# GND_STN.net
KiCad netlist of a schematic drawn in EAGLE
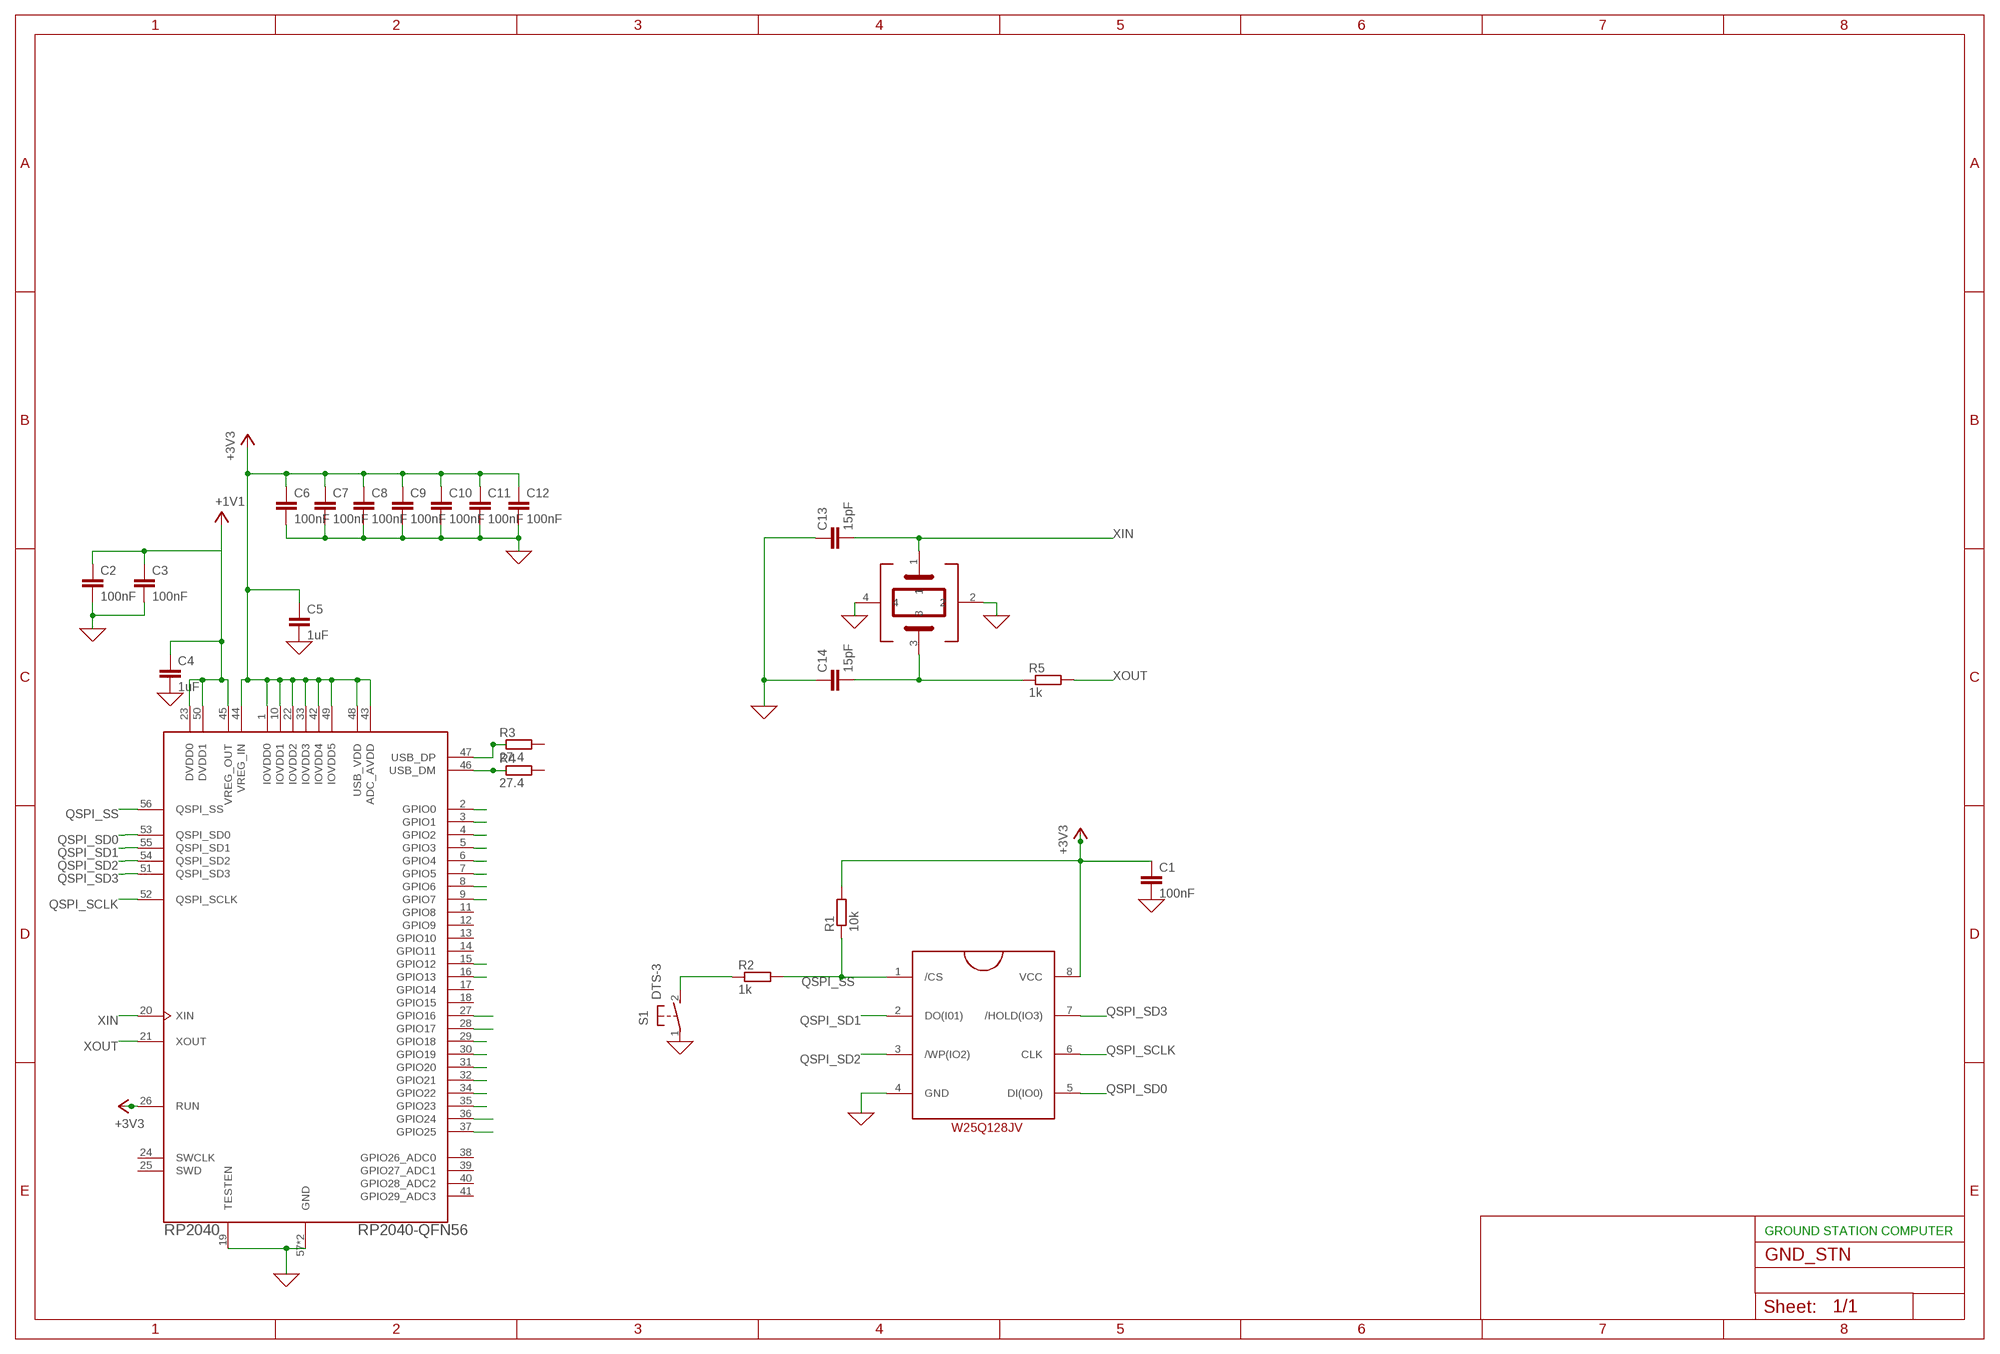
[diagram p0: schematic, sheet 1]

(export (version "E")
  (design (tool "Eeschema 10.0.6"))
  (components
    (comp (ref "C1")
      (value "100nF")
      (footprint "eagle-import:C0603")
      (libsource (lib "eagle-import") (part "C-EUC0603"))
    )
    (comp (ref "C2")
      (value "100nF")
      (footprint "eagle-import:C0603")
      (libsource (lib "eagle-import") (part "C-EUC0603"))
    )
    (comp (ref "C3")
      (value "100nF")
      (footprint "eagle-import:C0603")
      (libsource (lib "eagle-import") (part "C-EUC0603"))
    )
    (comp (ref "C4")
      (value "1uF")
      (footprint "eagle-import:C0603")
      (libsource (lib "eagle-import") (part "C-EUC0603"))
    )
    (comp (ref "C5")
      (value "1uF")
      (footprint "eagle-import:C0603")
      (libsource (lib "eagle-import") (part "C-EUC0603"))
    )
    (comp (ref "C6")
      (value "100nF")
      (footprint "eagle-import:C0603")
      (libsource (lib "eagle-import") (part "C-EUC0603"))
    )
    (comp (ref "C7")
      (value "100nF")
      (footprint "eagle-import:C0603")
      (libsource (lib "eagle-import") (part "C-EUC0603"))
    )
    (comp (ref "C8")
      (value "100nF")
      (footprint "eagle-import:C0603")
      (libsource (lib "eagle-import") (part "C-EUC0603"))
    )
    (comp (ref "C9")
      (value "100nF")
      (footprint "eagle-import:C0603")
      (libsource (lib "eagle-import") (part "C-EUC0603"))
    )
    (comp (ref "C10")
      (value "100nF")
      (footprint "eagle-import:C0603")
      (libsource (lib "eagle-import") (part "C-EUC0603"))
    )
    (comp (ref "C11")
      (value "100nF")
      (footprint "eagle-import:C0603")
      (libsource (lib "eagle-import") (part "C-EUC0603"))
    )
    (comp (ref "C12")
      (value "100nF")
      (footprint "eagle-import:C0603")
      (libsource (lib "eagle-import") (part "C-EUC0603"))
    )
    (comp (ref "C13")
      (value "15pF")
      (footprint "eagle-import:C0603")
      (libsource (lib "eagle-import") (part "C-EUC0603"))
    )
    (comp (ref "C14")
      (value "15pF")
      (footprint "eagle-import:C0603")
      (libsource (lib "eagle-import") (part "C-EUC0603"))
    )
    (comp (ref "R1")
      (value "10k")
      (footprint "eagle-import:R0603")
      (libsource (lib "eagle-import") (part "R-EU_R0603"))
    )
    (comp (ref "R2")
      (value "1k")
      (footprint "eagle-import:R0603")
      (libsource (lib "eagle-import") (part "R-EU_R0603"))
    )
    (comp (ref "R3")
      (value "27.4")
      (footprint "eagle-import:R0603")
      (libsource (lib "eagle-import") (part "R-EU_R0603"))
    )
    (comp (ref "R4")
      (value "27.4")
      (footprint "eagle-import:R0603")
      (libsource (lib "eagle-import") (part "R-EU_R0603"))
    )
    (comp (ref "R5")
      (value "1k")
      (footprint "eagle-import:R0603")
      (libsource (lib "eagle-import") (part "R-EU_R0603"))
    )
    (comp (ref "RP2040")
      (value "RP2040-QFN56")
      (footprint "eagle-import:RP2040-QFN-56")
      (libsource (lib "eagle-import") (part "RP2040-QFN56"))
    )
    (comp (ref "S1")
      (value "DTS-3")
      (footprint "eagle-import:DTS-3")
      (fields (field (name "MF") "APEM Inc."))
      (libsource (lib "eagle-import") (part "DTS-3"))
    )
    (comp (ref "U$1")
      (value "ABM8-272-T3")
      (footprint "eagle-import:ABM8-272-T3")
      (fields (field (name "MF") "ABRACON"))
      (libsource (lib "eagle-import") (part "ABM8-272-T3"))
    )
    (comp (ref "U2")
      (value "SOIC127P790X216-8NW25Q128JVJSQ")
      (footprint "eagle-import:SOIC127P790X216-8N")
      (libsource (lib "eagle-import") (part "SOIC127P790X216-8NW25Q128JVJSQ"))
    )
  )
  (nets
    (net (code "1") (name "+1V1") (class "Default")
      (node (ref "C2") (pin "1") (pinfunction "1_1") (pintype "passive"))
      (node (ref "C3") (pin "1") (pinfunction "1_1") (pintype "passive"))
      (node (ref "C4") (pin "1") (pinfunction "1_1") (pintype "passive"))
      (node (ref "RP2040") (pin "23") (pinfunction "DVDD0_23") (pintype "power_in"))
      (node (ref "RP2040") (pin "45") (pinfunction "VREG_OUT_45") (pintype "power_in"))
      (node (ref "RP2040") (pin "50") (pinfunction "DVDD1_50") (pintype "power_in"))
    )
    (net (code "2") (name "+3V3") (class "Default")
      (node (ref "C1") (pin "1") (pinfunction "1_1") (pintype "passive"))
      (node (ref "C10") (pin "1") (pinfunction "1_1") (pintype "passive"))
      (node (ref "C11") (pin "1") (pinfunction "1_1") (pintype "passive"))
      (node (ref "C12") (pin "1") (pinfunction "1_1") (pintype "passive"))
      (node (ref "C5") (pin "1") (pinfunction "1_1") (pintype "passive"))
      (node (ref "C6") (pin "1") (pinfunction "1_1") (pintype "passive"))
      (node (ref "C7") (pin "1") (pinfunction "1_1") (pintype "passive"))
      (node (ref "C8") (pin "1") (pinfunction "1_1") (pintype "passive"))
      (node (ref "C9") (pin "1") (pinfunction "1_1") (pintype "passive"))
      (node (ref "R1") (pin "2") (pinfunction "2_2") (pintype "passive"))
      (node (ref "RP2040") (pin "1") (pinfunction "IOVDD0_1") (pintype "power_in"))
      (node (ref "RP2040") (pin "10") (pinfunction "IOVDD1_10") (pintype "power_in"))
      (node (ref "RP2040") (pin "22") (pinfunction "IOVDD2_22") (pintype "power_in"))
      (node (ref "RP2040") (pin "26") (pinfunction "RUN_26") (pintype "input"))
      (node (ref "RP2040") (pin "33") (pinfunction "IOVDD3_33") (pintype "power_in"))
      (node (ref "RP2040") (pin "42") (pinfunction "IOVDD4_42") (pintype "power_in"))
      (node (ref "RP2040") (pin "43") (pinfunction "ADC_AVDD_43") (pintype "power_in"))
      (node (ref "RP2040") (pin "44") (pinfunction "VREG_IN_44") (pintype "power_in"))
      (node (ref "RP2040") (pin "48") (pinfunction "USB_VDD_48") (pintype "power_in"))
      (node (ref "RP2040") (pin "49") (pinfunction "IOVDD5_49") (pintype "power_in"))
      (node (ref "U2") (pin "8") (pinfunction "VCC_8") (pintype "bidirectional"))
    )
    (net (code "3") (name "/QSPI_SCLK") (class "Default")
      (node (ref "RP2040") (pin "52") (pinfunction "QSPI_SCLK_52") (pintype "output"))
      (node (ref "U2") (pin "6") (pinfunction "CLK_6") (pintype "bidirectional"))
    )
    (net (code "4") (name "/QSPI_SD0") (class "Default")
      (node (ref "RP2040") (pin "53") (pinfunction "QSPI_SD0_53") (pintype "bidirectional"))
      (node (ref "U2") (pin "5") (pinfunction "DI(IO0)_5") (pintype "bidirectional"))
    )
    (net (code "5") (name "/QSPI_SD1") (class "Default")
      (node (ref "RP2040") (pin "55") (pinfunction "QSPI_SD1_55") (pintype "bidirectional"))
      (node (ref "U2") (pin "2") (pinfunction "DO(I01)_2") (pintype "bidirectional"))
    )
    (net (code "6") (name "/QSPI_SD2") (class "Default")
      (node (ref "RP2040") (pin "54") (pinfunction "QSPI_SD2_54") (pintype "bidirectional"))
      (node (ref "U2") (pin "3") (pinfunction "/WP(IO2)_3") (pintype "bidirectional"))
    )
    (net (code "7") (name "/QSPI_SD3") (class "Default")
      (node (ref "RP2040") (pin "51") (pinfunction "QSPI_SD3_51") (pintype "bidirectional"))
      (node (ref "U2") (pin "7") (pinfunction "/HOLD(IO3)_7") (pintype "bidirectional"))
    )
    (net (code "8") (name "/QSPI_SS") (class "Default")
      (node (ref "R1") (pin "1") (pinfunction "1_1") (pintype "passive"))
      (node (ref "R2") (pin "2") (pinfunction "2_2") (pintype "passive"))
      (node (ref "RP2040") (pin "56") (pinfunction "QSPI_SS_56") (pintype "bidirectional"))
      (node (ref "U2") (pin "1") (pinfunction "/CS_1") (pintype "bidirectional"))
    )
    (net (code "9") (name "/XIN") (class "Default")
      (node (ref "C13") (pin "2") (pinfunction "2_2") (pintype "passive"))
      (node (ref "RP2040") (pin "20") (pinfunction "XIN_20") (pintype "input"))
      (node (ref "U$1") (pin "1") (pinfunction "1_1") (pintype "bidirectional"))
    )
    (net (code "10") (name "/XOUT") (class "Default")
      (node (ref "R5") (pin "2") (pinfunction "2_2") (pintype "passive"))
      (node (ref "RP2040") (pin "21") (pinfunction "XOUT_21") (pintype "passive"))
    )
    (net (code "11") (name "GND") (class "Default")
      (node (ref "C1") (pin "2") (pinfunction "2_2") (pintype "passive"))
      (node (ref "C10") (pin "2") (pinfunction "2_2") (pintype "passive"))
      (node (ref "C11") (pin "2") (pinfunction "2_2") (pintype "passive"))
      (node (ref "C12") (pin "2") (pinfunction "2_2") (pintype "passive"))
      (node (ref "C13") (pin "1") (pinfunction "1_1") (pintype "passive"))
      (node (ref "C14") (pin "1") (pinfunction "1_1") (pintype "passive"))
      (node (ref "C2") (pin "2") (pinfunction "2_2") (pintype "passive"))
      (node (ref "C3") (pin "2") (pinfunction "2_2") (pintype "passive"))
      (node (ref "C4") (pin "2") (pinfunction "2_2") (pintype "passive"))
      (node (ref "C5") (pin "2") (pinfunction "2_2") (pintype "passive"))
      (node (ref "C6") (pin "2") (pinfunction "2_2") (pintype "passive"))
      (node (ref "C7") (pin "2") (pinfunction "2_2") (pintype "passive"))
      (node (ref "C8") (pin "2") (pinfunction "2_2") (pintype "passive"))
      (node (ref "C9") (pin "2") (pinfunction "2_2") (pintype "passive"))
      (node (ref "RP2040") (pin "19") (pinfunction "TESTEN_19") (pintype "passive"))
      (node (ref "RP2040") (pin "57") (pinfunction "GND_57") (pintype "power_in"))
      (node (ref "RP2040") (pin "62") (pinfunction "GND_62") (pintype "power_in"))
      (node (ref "S1") (pin "1") (pinfunction "1_1") (pintype "passive"))
      (node (ref "U$1") (pin "2") (pinfunction "2_2") (pintype "bidirectional"))
      (node (ref "U$1") (pin "4") (pinfunction "4_4") (pintype "bidirectional"))
      (node (ref "U2") (pin "4") (pinfunction "GND_4") (pintype "bidirectional"))
    )
    (net (code "12") (name "Net-(C14-Pad2)") (class "Default")
      (node (ref "C14") (pin "2") (pinfunction "2_2") (pintype "passive"))
      (node (ref "R5") (pin "1") (pinfunction "1_1") (pintype "passive"))
      (node (ref "U$1") (pin "3") (pinfunction "3_3") (pintype "bidirectional"))
    )
    (net (code "13") (name "Net-(R2-Pad1)") (class "Default")
      (node (ref "R2") (pin "1") (pinfunction "1_1") (pintype "passive"))
      (node (ref "S1") (pin "2") (pinfunction "2_2") (pintype "passive"))
    )
    (net (code "14") (name "Net-(RP2040-USB_DM)") (class "Default")
      (node (ref "R4") (pin "1") (pinfunction "1_1") (pintype "passive"))
      (node (ref "RP2040") (pin "46") (pinfunction "USB_DM_46") (pintype "bidirectional"))
    )
    (net (code "15") (name "Net-(RP2040-USB_DP)") (class "Default")
      (node (ref "R3") (pin "1") (pinfunction "1_1") (pintype "passive"))
      (node (ref "RP2040") (pin "47") (pinfunction "USB_DP_47") (pintype "bidirectional"))
    )
    (net (code "16") (name "unconnected-(R3-Pad2)") (class "Default")
      (node (ref "R3") (pin "2") (pinfunction "2_2") (pintype "passive"))
    )
    (net (code "17") (name "unconnected-(R4-Pad2)") (class "Default")
      (node (ref "R4") (pin "2") (pinfunction "2_2") (pintype "passive"))
    )
    (net (code "18") (name "unconnected-(RP2040-GPIO0-Pad2)") (class "Default")
      (node (ref "RP2040") (pin "2") (pinfunction "GPIO0_2") (pintype "bidirectional"))
    )
    (net (code "19") (name "unconnected-(RP2040-GPIO1-Pad3)") (class "Default")
      (node (ref "RP2040") (pin "3") (pinfunction "GPIO1_3") (pintype "bidirectional"))
    )
    (net (code "20") (name "unconnected-(RP2040-GPIO2-Pad4)") (class "Default")
      (node (ref "RP2040") (pin "4") (pinfunction "GPIO2_4") (pintype "bidirectional"))
    )
    (net (code "21") (name "unconnected-(RP2040-GPIO3-Pad5)") (class "Default")
      (node (ref "RP2040") (pin "5") (pinfunction "GPIO3_5") (pintype "bidirectional"))
    )
    (net (code "22") (name "unconnected-(RP2040-GPIO4-Pad6)") (class "Default")
      (node (ref "RP2040") (pin "6") (pinfunction "GPIO4_6") (pintype "bidirectional"))
    )
    (net (code "23") (name "unconnected-(RP2040-GPIO5-Pad7)") (class "Default")
      (node (ref "RP2040") (pin "7") (pinfunction "GPIO5_7") (pintype "bidirectional"))
    )
    (net (code "24") (name "unconnected-(RP2040-GPIO6-Pad8)") (class "Default")
      (node (ref "RP2040") (pin "8") (pinfunction "GPIO6_8") (pintype "bidirectional"))
    )
    (net (code "25") (name "unconnected-(RP2040-GPIO7-Pad9)") (class "Default")
      (node (ref "RP2040") (pin "9") (pinfunction "GPIO7_9") (pintype "bidirectional"))
    )
    (net (code "26") (name "unconnected-(RP2040-GPIO8-Pad11)") (class "Default")
      (node (ref "RP2040") (pin "11") (pinfunction "GPIO8_11") (pintype "bidirectional"))
    )
    (net (code "27") (name "unconnected-(RP2040-GPIO9-Pad12)") (class "Default")
      (node (ref "RP2040") (pin "12") (pinfunction "GPIO9_12") (pintype "bidirectional"))
    )
    (net (code "28") (name "unconnected-(RP2040-GPIO10-Pad13)") (class "Default")
      (node (ref "RP2040") (pin "13") (pinfunction "GPIO10_13") (pintype "bidirectional"))
    )
    (net (code "29") (name "unconnected-(RP2040-GPIO11-Pad14)") (class "Default")
      (node (ref "RP2040") (pin "14") (pinfunction "GPIO11_14") (pintype "bidirectional"))
    )
    (net (code "30") (name "unconnected-(RP2040-GPIO12-Pad15)") (class "Default")
      (node (ref "RP2040") (pin "15") (pinfunction "GPIO12_15") (pintype "bidirectional"))
    )
    (net (code "31") (name "unconnected-(RP2040-GPIO13-Pad16)") (class "Default")
      (node (ref "RP2040") (pin "16") (pinfunction "GPIO13_16") (pintype "bidirectional"))
    )
    (net (code "32") (name "unconnected-(RP2040-GPIO14-Pad17)") (class "Default")
      (node (ref "RP2040") (pin "17") (pinfunction "GPIO14_17") (pintype "bidirectional"))
    )
    (net (code "33") (name "unconnected-(RP2040-GPIO15-Pad18)") (class "Default")
      (node (ref "RP2040") (pin "18") (pinfunction "GPIO15_18") (pintype "bidirectional"))
    )
    (net (code "34") (name "unconnected-(RP2040-GPIO16-Pad27)") (class "Default")
      (node (ref "RP2040") (pin "27") (pinfunction "GPIO16_27") (pintype "bidirectional"))
    )
    (net (code "35") (name "unconnected-(RP2040-GPIO17-Pad28)") (class "Default")
      (node (ref "RP2040") (pin "28") (pinfunction "GPIO17_28") (pintype "bidirectional"))
    )
    (net (code "36") (name "unconnected-(RP2040-GPIO18-Pad29)") (class "Default")
      (node (ref "RP2040") (pin "29") (pinfunction "GPIO18_29") (pintype "bidirectional"))
    )
    (net (code "37") (name "unconnected-(RP2040-GPIO19-Pad30)") (class "Default")
      (node (ref "RP2040") (pin "30") (pinfunction "GPIO19_30") (pintype "bidirectional"))
    )
    (net (code "38") (name "unconnected-(RP2040-GPIO20-Pad31)") (class "Default")
      (node (ref "RP2040") (pin "31") (pinfunction "GPIO20_31") (pintype "bidirectional"))
    )
    (net (code "39") (name "unconnected-(RP2040-GPIO21-Pad32)") (class "Default")
      (node (ref "RP2040") (pin "32") (pinfunction "GPIO21_32") (pintype "bidirectional"))
    )
    (net (code "40") (name "unconnected-(RP2040-GPIO22-Pad34)") (class "Default")
      (node (ref "RP2040") (pin "34") (pinfunction "GPIO22_34") (pintype "bidirectional"))
    )
    (net (code "41") (name "unconnected-(RP2040-GPIO23-Pad35)") (class "Default")
      (node (ref "RP2040") (pin "35") (pinfunction "GPIO23_35") (pintype "bidirectional"))
    )
    (net (code "42") (name "unconnected-(RP2040-GPIO24-Pad36)") (class "Default")
      (node (ref "RP2040") (pin "36") (pinfunction "GPIO24_36") (pintype "bidirectional"))
    )
    (net (code "43") (name "unconnected-(RP2040-GPIO25-Pad37)") (class "Default")
      (node (ref "RP2040") (pin "37") (pinfunction "GPIO25_37") (pintype "bidirectional"))
    )
    (net (code "44") (name "unconnected-(RP2040-GPIO26_ADC0-Pad38)") (class "Default")
      (node (ref "RP2040") (pin "38") (pinfunction "GPIO26_ADC0_38") (pintype "bidirectional"))
    )
    (net (code "45") (name "unconnected-(RP2040-GPIO27_ADC1-Pad39)") (class "Default")
      (node (ref "RP2040") (pin "39") (pinfunction "GPIO27_ADC1_39") (pintype "bidirectional"))
    )
    (net (code "46") (name "unconnected-(RP2040-GPIO28_ADC2-Pad40)") (class "Default")
      (node (ref "RP2040") (pin "40") (pinfunction "GPIO28_ADC2_40") (pintype "bidirectional"))
    )
    (net (code "47") (name "unconnected-(RP2040-GPIO29_ADC3-Pad41)") (class "Default")
      (node (ref "RP2040") (pin "41") (pinfunction "GPIO29_ADC3_41") (pintype "bidirectional"))
    )
    (net (code "48") (name "unconnected-(RP2040-SWCLK-Pad24)") (class "Default")
      (node (ref "RP2040") (pin "24") (pinfunction "SWCLK_24") (pintype "output"))
    )
    (net (code "49") (name "unconnected-(RP2040-SWD-Pad25)") (class "Default")
      (node (ref "RP2040") (pin "25") (pinfunction "SWD_25") (pintype "bidirectional"))
    )
  )
)
